# Sheet1.net
KiCad netlist of a schematic drawn in Altium Designer
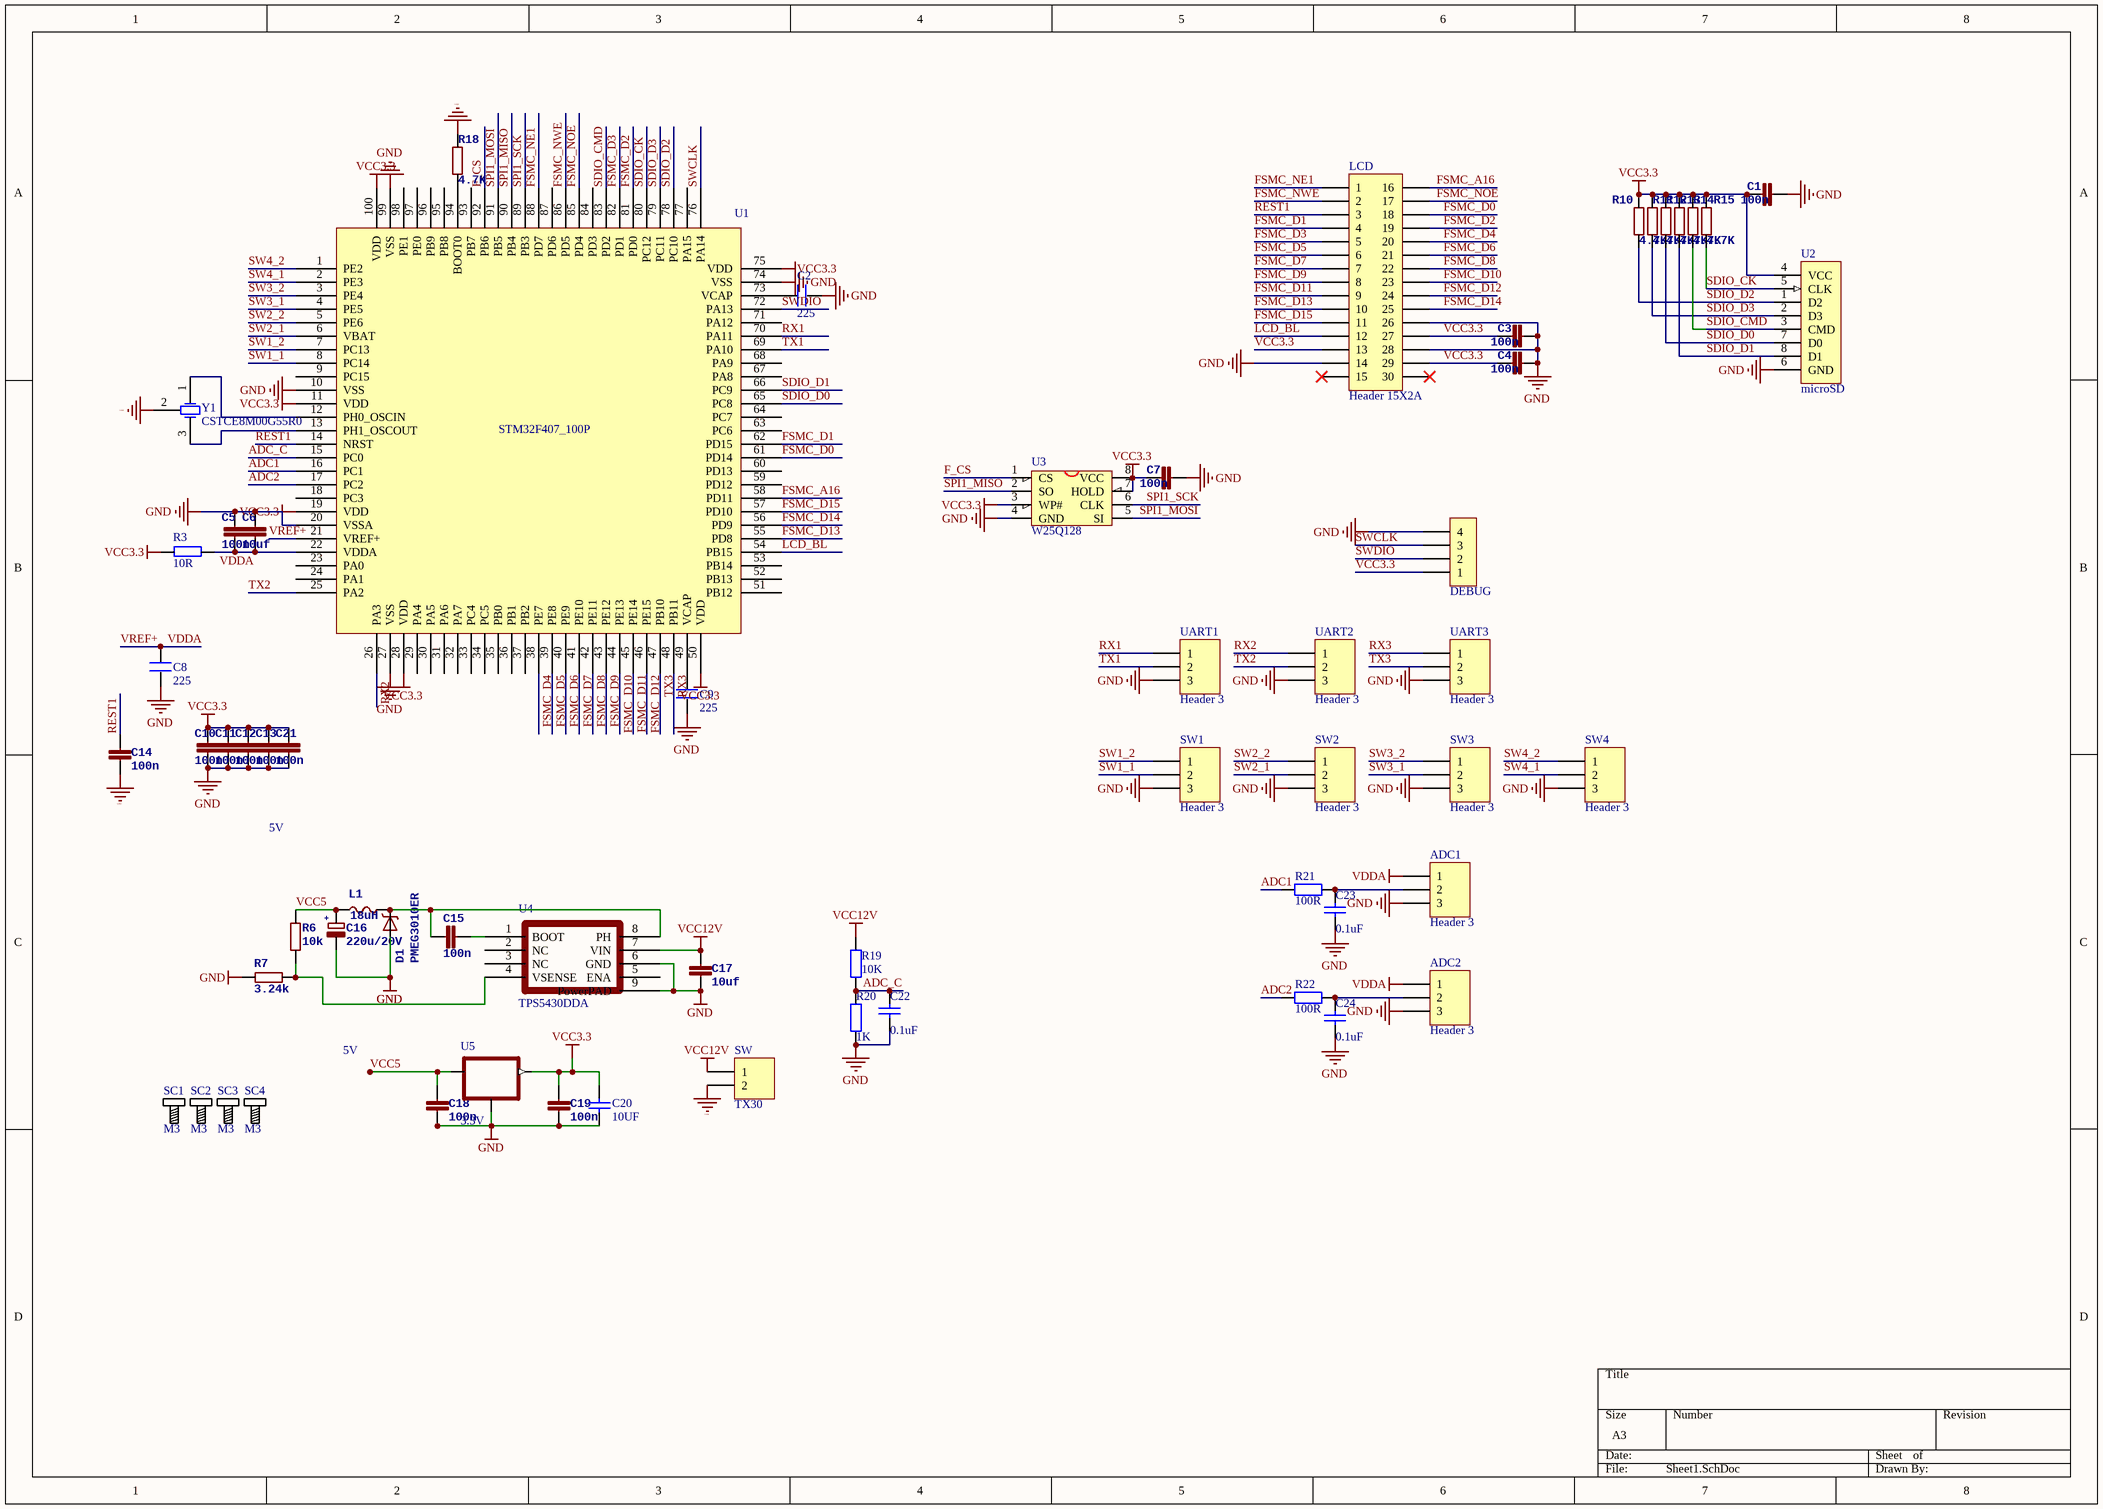
[diagram p0: Sheet1.SchDoc]

(export (version "E")
  (design (tool "Eeschema 10.0.6"))
  (components
    (comp (ref "ADC1")
      (value "Header 3")
      (footprint "3PJST1.25")
      (description "Header, 3-Pin")
      (fields (field (name "PUBLISHER") "Altium Limited"))
      (libsource (lib "Miscellaneous Connectors") (part "Header 3"))
    )
    (comp (ref "ADC2")
      (value "Header 3")
      (footprint "3PJST1.25")
      (description "Header, 3-Pin")
      (fields (field (name "PUBLISHER") "Altium Limited"))
      (libsource (lib "Miscellaneous Connectors") (part "Header 3"))
    )
    (comp (ref "C1")
      (value "100n")
      (footprint "C0603")
      (description "CAPACITOR, European symbol")
      (libsource (lib "") (part "C-EUC0603_1"))
    )
    (comp (ref "C2") (value "225") (footprint "C0603") (libsource (lib "Explorer STM32F407封装库") (part "C")))
    (comp (ref "C3")
      (value "100n")
      (footprint "C0603")
      (description "CAPACITOR, European symbol")
      (libsource (lib "") (part "C-EUC0603_1"))
    )
    (comp (ref "C4")
      (value "100n")
      (footprint "C0603")
      (description "CAPACITOR, European symbol")
      (libsource (lib "") (part "C-EUC0603_1"))
    )
    (comp (ref "C5")
      (value "100n")
      (footprint "C0603")
      (description "CAPACITOR, European symbol")
      (libsource (lib "TZJLIB") (part "C-EUC0603"))
    )
    (comp (ref "C6")
      (value "10uf")
      (footprint "C0603")
      (description "CAPACITOR, European symbol")
      (libsource (lib "TZJLIB") (part "C-EUC0603"))
    )
    (comp (ref "C7")
      (value "100n")
      (footprint "C0603")
      (description "CAPACITOR, European symbol")
      (libsource (lib "") (part "C-EUC0603_1"))
    )
    (comp (ref "C8") (value "225") (footprint "C0603") (libsource (lib "Explorer STM32F407封装库") (part "C")))
    (comp (ref "C9") (value "225") (footprint "C0603") (libsource (lib "Explorer STM32F407封装库") (part "C")))
    (comp (ref "C10")
      (value "100n")
      (footprint "C0603")
      (description "CAPACITOR, European symbol")
      (libsource (lib "TZJLIB") (part "C-EUC0603"))
    )
    (comp (ref "C11")
      (value "100n")
      (footprint "C0603")
      (description "CAPACITOR, European symbol")
      (libsource (lib "TZJLIB") (part "C-EUC0603"))
    )
    (comp (ref "C12")
      (value "100n")
      (footprint "C0603")
      (description "CAPACITOR, European symbol")
      (libsource (lib "TZJLIB") (part "C-EUC0603"))
    )
    (comp (ref "C13")
      (value "100n")
      (footprint "C0603")
      (description "CAPACITOR, European symbol")
      (libsource (lib "TZJLIB") (part "C-EUC0603"))
    )
    (comp (ref "C14")
      (value "100n")
      (footprint "C0603")
      (description "CAPACITOR, European symbol")
      (libsource (lib "TZJLIB") (part "C-EUC0603"))
    )
    (comp (ref "C15")
      (value "100n")
      (footprint "C0603")
      (description "CAPACITOR, European symbol")
      (libsource (lib "") (part "C-EUC0603_1"))
    )
    (comp (ref "C16")
      (value "220u/20V")
      (footprint "SMC_B")
      (description "POLARIZED CAPACITOR, European symbol")
      (fields (field (name "+") "+"))
      (libsource (lib "rcl") (part "CPOL-EUSMCB"))
    )
    (comp (ref "C17")
      (value "10uf")
      (footprint "C0603")
      (description "CAPACITOR, European symbol")
      (libsource (lib "rcl") (part "C-EUC0603"))
    )
    (comp (ref "C18")
      (value "100n")
      (footprint "C0603")
      (description "CAPACITOR, European symbol")
      (libsource (lib "rcl") (part "C-EUC0603"))
    )
    (comp (ref "C19")
      (value "100n")
      (footprint "C0603")
      (description "CAPACITOR, European symbol")
      (libsource (lib "rcl") (part "C-EUC0603"))
    )
    (comp (ref "C20")
      (value "10UF")
      (footprint "C0603")
      (description "Capacitor")
      (fields (field (name "PUBLISHER") "Altium Limited"))
      (libsource (lib "Miscellaneous Devices") (part "Cap"))
    )
    (comp (ref "C21")
      (value "100n")
      (footprint "C0603")
      (description "CAPACITOR, European symbol")
      (libsource (lib "TZJLIB") (part "C-EUC0603"))
    )
    (comp (ref "C22")
      (value "0.1uF")
      (footprint "C0603")
      (description "Capacitor")
      (fields (field (name "PUBLISHER") "Altium Limited"))
      (libsource (lib "Miscellaneous Devices") (part "Cap"))
    )
    (comp (ref "C23")
      (value "0.1uF")
      (footprint "C0603")
      (description "Capacitor")
      (fields (field (name "PUBLISHER") "Altium Limited"))
      (libsource (lib "Miscellaneous Devices") (part "Cap"))
    )
    (comp (ref "C24")
      (value "0.1uF")
      (footprint "C0603")
      (description "Capacitor")
      (fields (field (name "PUBLISHER") "Altium Limited"))
      (libsource (lib "Miscellaneous Devices") (part "Cap"))
    )
    (comp (ref "D1")
      (value "PMEG3010ER")
      (footprint "SOD123W-DIODE - AK")
      (libsource (lib "TZJLIB") (part "DIODE-SCHOTTKYSOD123-W"))
    )
    (comp (ref "DEBUG") (value "CON4") (footprint "DF13-1.25-4A") (libsource (lib "原理图封装库") (part "CON4")))
    (comp (ref "L1") (value "18uH") (footprint "L7_7_4") (libsource (lib "BGC1.0") (part "L-EU_L0603")))
    (comp (ref "LCD")
      (value "Header 15X2A")
      (footprint "DIP1.0X30")
      (description "Header, 15-Pin, Dual row")
      (fields (field (name "PUBLISHER") "Altium Limited"))
      (libsource (lib "Miscellaneous Connectors") (part "Header 15X2A"))
    )
    (comp (ref "R3") (value "10R") (footprint "R0603") (libsource (lib "Explorer STM32F407封装库") (part "R")))
    (comp (ref "R6")
      (value "10k")
      (footprint "R0603")
      (description "RESISTOR, European symbol")
      (libsource (lib "rcl") (part "R-EU_R0603"))
    )
    (comp (ref "R7")
      (value "3.24k")
      (footprint "R0603")
      (description "RESISTOR, European symbol")
      (libsource (lib "rcl") (part "R-EU_R0603"))
    )
    (comp (ref "R10")
      (value "4.7K")
      (footprint "R0603")
      (description "RESISTOR, European symbol")
      (libsource (lib "rcl") (part "R-EU_R0603"))
    )
    (comp (ref "R11")
      (value "4.7K")
      (footprint "R0603")
      (description "RESISTOR, European symbol")
      (libsource (lib "rcl") (part "R-EU_R0603"))
    )
    (comp (ref "R12")
      (value "4.7K")
      (footprint "R0603")
      (description "RESISTOR, European symbol")
      (libsource (lib "rcl") (part "R-EU_R0603"))
    )
    (comp (ref "R13")
      (value "4.7K")
      (footprint "R0603")
      (description "RESISTOR, European symbol")
      (libsource (lib "rcl") (part "R-EU_R0603"))
    )
    (comp (ref "R14")
      (value "4.7K")
      (footprint "R0603")
      (description "RESISTOR, European symbol")
      (libsource (lib "rcl") (part "R-EU_R0603"))
    )
    (comp (ref "R15")
      (value "4.7K")
      (footprint "R0603")
      (description "RESISTOR, European symbol")
      (libsource (lib "rcl") (part "R-EU_R0603"))
    )
    (comp (ref "R18")
      (value "4.7K")
      (footprint "R0603")
      (description "RESISTOR, European symbol")
      (libsource (lib "rcl") (part "R-EU_R0603"))
    )
    (comp (ref "R19")
      (value "10K")
      (footprint "R0603")
      (description "Resistor")
      (fields (field (name "PUBLISHER") "Altium Limited"))
      (libsource (lib "") (part "Res2_1"))
    )
    (comp (ref "R20")
      (value "1K")
      (footprint "R0603")
      (description "Resistor")
      (fields (field (name "Comment") "10K") (field (name "PUBLISHER") "Altium Limited"))
      (libsource (lib "") (part "Res2_1"))
    )
    (comp (ref "R21")
      (value "100R")
      (footprint "R0603")
      (description "Resistor")
      (fields (field (name "Comment") "10K") (field (name "PUBLISHER") "Altium Limited"))
      (libsource (lib "Miscellaneous Devices") (part "Res2"))
    )
    (comp (ref "R22")
      (value "100R")
      (footprint "R0603")
      (description "Resistor")
      (fields (field (name "Comment") "10K") (field (name "PUBLISHER") "Altium Limited"))
      (libsource (lib "Miscellaneous Devices") (part "Res2"))
    )
    (comp (ref "SC1")
      (value "M3")
      (footprint "TZJLIB:SCRREW_M3")
      (description "Screw")
      (libsource (lib "MY") (part "Screw_M3"))
    )
    (comp (ref "SC2")
      (value "M3")
      (footprint "SCRREW_M3")
      (description "Screw")
      (libsource (lib "MY") (part "Screw_M3"))
    )
    (comp (ref "SC3")
      (value "M3")
      (footprint "SCRREW_M3")
      (description "Screw")
      (libsource (lib "MY") (part "Screw_M3"))
    )
    (comp (ref "SC4")
      (value "M3")
      (footprint "SCRREW_M3")
      (description "Screw")
      (libsource (lib "MY") (part "Screw_M3"))
    )
    (comp (ref "SW")
      (value "TX30")
      (footprint "TX30-m")
      (description "Header, 2-Pin")
      (fields (field (name "PUBLISHER") "Altium Limited"))
      (libsource (lib "Miscellaneous Connectors") (part "Header 2"))
    )
    (comp (ref "SW1")
      (value "Header 3")
      (footprint "3PJST1.25")
      (description "Header, 3-Pin")
      (fields (field (name "PUBLISHER") "Altium Limited"))
      (libsource (lib "Miscellaneous Connectors") (part "Header 3"))
    )
    (comp (ref "SW2")
      (value "Header 3")
      (footprint "3PJST1.25")
      (description "Header, 3-Pin")
      (fields (field (name "PUBLISHER") "Altium Limited"))
      (libsource (lib "Miscellaneous Connectors") (part "Header 3"))
    )
    (comp (ref "SW3")
      (value "Header 3")
      (footprint "3PJST1.25")
      (description "Header, 3-Pin")
      (fields (field (name "PUBLISHER") "Altium Limited"))
      (libsource (lib "Miscellaneous Connectors") (part "Header 3"))
    )
    (comp (ref "SW4")
      (value "Header 3")
      (footprint "3PJST1.25")
      (description "Header, 3-Pin")
      (fields (field (name "PUBLISHER") "Altium Limited"))
      (libsource (lib "Miscellaneous Connectors") (part "Header 3"))
    )
    (comp (ref "U1")
      (value "STM32F407_100P")
      (footprint "ST_LQFP100")
      (libsource (lib "TZJLIB") (part "STM32F407_100P"))
    )
    (comp (ref "U2")
      (value "microSD")
      (footprint "MICROSD1")
      (libsource (lib "004-Controller") (part "microSD"))
    )
    (comp (ref "U3")
      (value "W25Q128")
      (footprint "SOIC-8")
      (description "W25X16;SST25VF016;MX25L1605")
      (libsource (lib "TZJLIB") (part "W25X16"))
    )
    (comp (ref "U4") (value "TPS5430DDA") (footprint "SOIC") (libsource (lib "BGC1.0") (part "TPS5430DDA")))
    (comp (ref "U5") (value "3.3V") (footprint "SOT23") (libsource (lib "BGC1.0") (part "XC6206")))
    (comp (ref "UART1")
      (value "Header 3")
      (footprint "3PJST1.25")
      (description "Header, 3-Pin")
      (fields (field (name "PUBLISHER") "Altium Limited"))
      (libsource (lib "Miscellaneous Connectors") (part "Header 3"))
    )
    (comp (ref "UART2")
      (value "Header 3")
      (footprint "3PJST1.25")
      (description "Header, 3-Pin")
      (fields (field (name "PUBLISHER") "Altium Limited"))
      (libsource (lib "Miscellaneous Connectors") (part "Header 3"))
    )
    (comp (ref "UART3")
      (value "Header 3")
      (footprint "3PJST1.25")
      (description "Header, 3-Pin")
      (fields (field (name "PUBLISHER") "Altium Limited"))
      (libsource (lib "Miscellaneous Connectors") (part "Header 3"))
    )
    (comp (ref "Y1")
      (value "CSTCE8M00G55R0")
      (footprint "CRYSMD3.2X1.3")
      (libsource (lib "airtops-L") (part "XTAL-3"))
    )
  )
  (nets
    (net (code "1") (name "/ADC1") (class "Default")
      (node (ref "R21") (pin "1") (pinfunction "1_1") (pintype "passive"))
      (node (ref "U1") (pin "16") (pinfunction "PC1_16") (pintype "passive"))
    )
    (net (code "2") (name "/ADC2") (class "Default")
      (node (ref "R22") (pin "1") (pinfunction "1_1") (pintype "passive"))
      (node (ref "U1") (pin "17") (pinfunction "PC2_17") (pintype "passive"))
    )
    (net (code "3") (name "/ADC_C") (class "Default")
      (node (ref "C22") (pin "2") (pinfunction "2_2") (pintype "passive"))
      (node (ref "R19") (pin "2") (pinfunction "2_2") (pintype "passive"))
      (node (ref "R20") (pin "1") (pinfunction "1_1") (pintype "passive"))
      (node (ref "U1") (pin "15") (pinfunction "PC0_15") (pintype "passive"))
    )
    (net (code "4") (name "/FSMC_A16") (class "Default")
      (node (ref "LCD") (pin "16") (pinfunction "16_16") (pintype "passive"))
      (node (ref "U1") (pin "58") (pinfunction "PD11_58") (pintype "passive"))
    )
    (net (code "5") (name "/FSMC_D0") (class "Default")
      (node (ref "LCD") (pin "18") (pinfunction "18_18") (pintype "passive"))
      (node (ref "U1") (pin "61") (pinfunction "PD14_61") (pintype "passive"))
    )
    (net (code "6") (name "/FSMC_D1") (class "Default")
      (node (ref "LCD") (pin "4") (pinfunction "4_4") (pintype "passive"))
      (node (ref "U1") (pin "62") (pinfunction "PD15_62") (pintype "passive"))
    )
    (net (code "7") (name "/FSMC_D2") (class "Default")
      (node (ref "LCD") (pin "19") (pinfunction "19_19") (pintype "passive"))
      (node (ref "U1") (pin "81") (pinfunction "PD0_81") (pintype "passive"))
    )
    (net (code "8") (name "/FSMC_D3") (class "Default")
      (node (ref "LCD") (pin "5") (pinfunction "5_5") (pintype "passive"))
      (node (ref "U1") (pin "82") (pinfunction "PD1_82") (pintype "passive"))
    )
    (net (code "9") (name "/FSMC_D4") (class "Default")
      (node (ref "LCD") (pin "20") (pinfunction "20_20") (pintype "passive"))
      (node (ref "U1") (pin "38") (pinfunction "PE7_38") (pintype "passive"))
    )
    (net (code "10") (name "/FSMC_D5") (class "Default")
      (node (ref "LCD") (pin "6") (pinfunction "6_6") (pintype "passive"))
      (node (ref "U1") (pin "39") (pinfunction "PE8_39") (pintype "passive"))
    )
    (net (code "11") (name "/FSMC_D6") (class "Default")
      (node (ref "LCD") (pin "21") (pinfunction "21_21") (pintype "passive"))
      (node (ref "U1") (pin "40") (pinfunction "PE9_40") (pintype "passive"))
    )
    (net (code "12") (name "/FSMC_D7") (class "Default")
      (node (ref "LCD") (pin "7") (pinfunction "7_7") (pintype "passive"))
      (node (ref "U1") (pin "41") (pinfunction "PE10_41") (pintype "passive"))
    )
    (net (code "13") (name "/FSMC_D8") (class "Default")
      (node (ref "LCD") (pin "22") (pinfunction "22_22") (pintype "passive"))
      (node (ref "U1") (pin "42") (pinfunction "PE11_42") (pintype "passive"))
    )
    (net (code "14") (name "/FSMC_D9") (class "Default")
      (node (ref "LCD") (pin "8") (pinfunction "8_8") (pintype "passive"))
      (node (ref "U1") (pin "43") (pinfunction "PE12_43") (pintype "passive"))
    )
    (net (code "15") (name "/FSMC_D10") (class "Default")
      (node (ref "LCD") (pin "23") (pinfunction "23_23") (pintype "passive"))
      (node (ref "U1") (pin "44") (pinfunction "PE13_44") (pintype "passive"))
    )
    (net (code "16") (name "/FSMC_D11") (class "Default")
      (node (ref "LCD") (pin "9") (pinfunction "9_9") (pintype "passive"))
      (node (ref "U1") (pin "45") (pinfunction "PE14_45") (pintype "passive"))
    )
    (net (code "17") (name "/FSMC_D12") (class "Default")
      (node (ref "LCD") (pin "24") (pinfunction "24_24") (pintype "passive"))
      (node (ref "U1") (pin "46") (pinfunction "PE15_46") (pintype "passive"))
    )
    (net (code "18") (name "/FSMC_D13") (class "Default")
      (node (ref "LCD") (pin "10") (pinfunction "10_10") (pintype "passive"))
      (node (ref "U1") (pin "55") (pinfunction "PD8_55") (pintype "passive"))
    )
    (net (code "19") (name "/FSMC_D14") (class "Default")
      (node (ref "LCD") (pin "25") (pinfunction "25_25") (pintype "passive"))
      (node (ref "U1") (pin "56") (pinfunction "PD9_56") (pintype "passive"))
    )
    (net (code "20") (name "/FSMC_D15") (class "Default")
      (node (ref "LCD") (pin "11") (pinfunction "11_11") (pintype "passive"))
      (node (ref "U1") (pin "57") (pinfunction "PD10_57") (pintype "passive"))
    )
    (net (code "21") (name "/FSMC_NE1") (class "Default")
      (node (ref "LCD") (pin "1") (pinfunction "1_1") (pintype "passive"))
      (node (ref "U1") (pin "88") (pinfunction "PD7_88") (pintype "passive"))
    )
    (net (code "22") (name "/FSMC_NOE") (class "Default")
      (node (ref "LCD") (pin "17") (pinfunction "17_17") (pintype "passive"))
      (node (ref "U1") (pin "85") (pinfunction "PD4_85") (pintype "passive"))
    )
    (net (code "23") (name "/FSMC_NWE") (class "Default")
      (node (ref "LCD") (pin "2") (pinfunction "2_2") (pintype "passive"))
      (node (ref "U1") (pin "86") (pinfunction "PD5_86") (pintype "passive"))
    )
    (net (code "24") (name "/F_CS") (class "Default")
      (node (ref "U1") (pin "92") (pinfunction "PB6_92") (pintype "passive"))
      (node (ref "U3") (pin "1") (pinfunction "CS_1") (pintype "passive"))
    )
    (net (code "25") (name "/LCD_BL") (class "Default")
      (node (ref "LCD") (pin "12") (pinfunction "12_12") (pintype "passive"))
      (node (ref "U1") (pin "54") (pinfunction "PB15_54") (pintype "passive"))
    )
    (net (code "26") (name "/REST1") (class "Default")
      (node (ref "C14") (pin "2") (pinfunction "2_2") (pintype "passive"))
      (node (ref "LCD") (pin "3") (pinfunction "3_3") (pintype "passive"))
      (node (ref "U1") (pin "14") (pinfunction "NRST_14") (pintype "passive"))
    )
    (net (code "27") (name "/RX1") (class "Default")
      (node (ref "U1") (pin "70") (pinfunction "PA11_70") (pintype "passive"))
      (node (ref "UART1") (pin "1") (pinfunction "1_1") (pintype "passive"))
    )
    (net (code "28") (name "/RX2") (class "Default")
      (node (ref "U1") (pin "26") (pinfunction "PA3_26") (pintype "passive"))
      (node (ref "UART2") (pin "1") (pinfunction "1_1") (pintype "passive"))
    )
    (net (code "29") (name "/RX3") (class "Default")
      (node (ref "U1") (pin "48") (pinfunction "PB11_48") (pintype "passive"))
      (node (ref "UART3") (pin "1") (pinfunction "1_1") (pintype "passive"))
    )
    (net (code "30") (name "/SDIO_CK") (class "Default")
      (node (ref "R15") (pin "1") (pinfunction "1_1") (pintype "passive"))
      (node (ref "U1") (pin "80") (pinfunction "PC12_80") (pintype "passive"))
      (node (ref "U2") (pin "5") (pinfunction "CLK_5") (pintype "input"))
    )
    (net (code "31") (name "/SDIO_CMD") (class "Default")
      (node (ref "R14") (pin "1") (pinfunction "1_1") (pintype "passive"))
      (node (ref "U1") (pin "83") (pinfunction "PD2_83") (pintype "passive"))
      (node (ref "U2") (pin "3") (pinfunction "CMD_3") (pintype "passive"))
    )
    (net (code "32") (name "/SDIO_D0") (class "Default")
      (node (ref "R12") (pin "1") (pinfunction "1_1") (pintype "passive"))
      (node (ref "U1") (pin "65") (pinfunction "PC8_65") (pintype "passive"))
      (node (ref "U2") (pin "7") (pinfunction "D0_7") (pintype "passive"))
    )
    (net (code "33") (name "/SDIO_D1") (class "Default")
      (node (ref "R13") (pin "1") (pinfunction "1_1") (pintype "passive"))
      (node (ref "U1") (pin "66") (pinfunction "PC9_66") (pintype "passive"))
      (node (ref "U2") (pin "8") (pinfunction "D1_8") (pintype "passive"))
    )
    (net (code "34") (name "/SDIO_D2") (class "Default")
      (node (ref "R10") (pin "1") (pinfunction "1_1") (pintype "passive"))
      (node (ref "U1") (pin "78") (pinfunction "PC10_78") (pintype "passive"))
      (node (ref "U2") (pin "1") (pinfunction "D2_1") (pintype "passive"))
    )
    (net (code "35") (name "/SDIO_D3") (class "Default")
      (node (ref "R11") (pin "1") (pinfunction "1_1") (pintype "passive"))
      (node (ref "U1") (pin "79") (pinfunction "PC11_79") (pintype "passive"))
      (node (ref "U2") (pin "2") (pinfunction "D3_2") (pintype "passive"))
    )
    (net (code "36") (name "/SPI1_MISO") (class "Default")
      (node (ref "U1") (pin "90") (pinfunction "PB4_90") (pintype "passive"))
      (node (ref "U3") (pin "2") (pinfunction "SO_2") (pintype "passive"))
    )
    (net (code "37") (name "/SPI1_MOSI") (class "Default")
      (node (ref "U1") (pin "91") (pinfunction "PB5_91") (pintype "passive"))
      (node (ref "U3") (pin "5") (pinfunction "SI_5") (pintype "passive"))
    )
    (net (code "38") (name "/SPI1_SCK") (class "Default")
      (node (ref "U1") (pin "89") (pinfunction "PB3_89") (pintype "passive"))
      (node (ref "U3") (pin "6") (pinfunction "CLK_6") (pintype "passive"))
    )
    (net (code "39") (name "/SW1_1") (class "Default")
      (node (ref "SW1") (pin "2") (pinfunction "2_2") (pintype "passive"))
      (node (ref "U1") (pin "8") (pinfunction "PC14_8") (pintype "passive"))
    )
    (net (code "40") (name "/SW1_2") (class "Default")
      (node (ref "SW1") (pin "1") (pinfunction "1_1") (pintype "passive"))
      (node (ref "U1") (pin "7") (pinfunction "PC13_7") (pintype "passive"))
    )
    (net (code "41") (name "/SW2_1") (class "Default")
      (node (ref "SW2") (pin "2") (pinfunction "2_2") (pintype "passive"))
      (node (ref "U1") (pin "6") (pinfunction "VBAT_6") (pintype "passive"))
    )
    (net (code "42") (name "/SW2_2") (class "Default")
      (node (ref "SW2") (pin "1") (pinfunction "1_1") (pintype "passive"))
      (node (ref "U1") (pin "5") (pinfunction "PE6_5") (pintype "passive"))
    )
    (net (code "43") (name "/SW3_1") (class "Default")
      (node (ref "SW3") (pin "2") (pinfunction "2_2") (pintype "passive"))
      (node (ref "U1") (pin "4") (pinfunction "PE5_4") (pintype "passive"))
    )
    (net (code "44") (name "/SW3_2") (class "Default")
      (node (ref "SW3") (pin "1") (pinfunction "1_1") (pintype "passive"))
      (node (ref "U1") (pin "3") (pinfunction "PE4_3") (pintype "passive"))
    )
    (net (code "45") (name "/SW4_1") (class "Default")
      (node (ref "SW4") (pin "2") (pinfunction "2_2") (pintype "passive"))
      (node (ref "U1") (pin "2") (pinfunction "PE3_2") (pintype "passive"))
    )
    (net (code "46") (name "/SW4_2") (class "Default")
      (node (ref "SW4") (pin "1") (pinfunction "1_1") (pintype "passive"))
      (node (ref "U1") (pin "1") (pinfunction "PE2_1") (pintype "passive"))
    )
    (net (code "47") (name "/SWCLK") (class "Default")
      (node (ref "DEBUG") (pin "3") (pinfunction "3_3") (pintype "passive"))
      (node (ref "U1") (pin "76") (pinfunction "PA14_76") (pintype "passive"))
    )
    (net (code "48") (name "/SWDIO") (class "Default")
      (node (ref "DEBUG") (pin "2") (pinfunction "2_2") (pintype "passive"))
      (node (ref "U1") (pin "72") (pinfunction "PA13_72") (pintype "passive"))
    )
    (net (code "49") (name "/TX1") (class "Default")
      (node (ref "U1") (pin "69") (pinfunction "PA10_69") (pintype "passive"))
      (node (ref "UART1") (pin "2") (pinfunction "2_2") (pintype "passive"))
    )
    (net (code "50") (name "/TX2") (class "Default")
      (node (ref "U1") (pin "25") (pinfunction "PA2_25") (pintype "passive"))
      (node (ref "UART2") (pin "2") (pinfunction "2_2") (pintype "passive"))
    )
    (net (code "51") (name "/TX3") (class "Default")
      (node (ref "U1") (pin "47") (pinfunction "PB10_47") (pintype "passive"))
      (node (ref "UART3") (pin "2") (pinfunction "2_2") (pintype "passive"))
    )
    (net (code "52") (name "/VCC5") (class "Default")
      (node (ref "C16") (pin "+") (pinfunction "+_+") (pintype "passive"))
      (node (ref "C18") (pin "1") (pinfunction "1_1") (pintype "passive"))
      (node (ref "L1") (pin "1") (pinfunction "1_1") (pintype "passive"))
      (node (ref "R6") (pin "2") (pinfunction "2_2") (pintype "passive"))
      (node (ref "U5") (pin "3") (pinfunction "IN_3") (pintype "passive"))
    )
    (net (code "53") (name "GND") (class "Default")
      (node (ref "ADC1") (pin "3") (pinfunction "3_3") (pintype "passive"))
      (node (ref "ADC2") (pin "3") (pinfunction "3_3") (pintype "passive"))
      (node (ref "C1") (pin "2") (pinfunction "2_2") (pintype "passive"))
      (node (ref "C10") (pin "1") (pinfunction "1_1") (pintype "passive"))
      (node (ref "C11") (pin "1") (pinfunction "1_1") (pintype "passive"))
      (node (ref "C12") (pin "1") (pinfunction "1_1") (pintype "passive"))
      (node (ref "C13") (pin "1") (pinfunction "1_1") (pintype "passive"))
      (node (ref "C14") (pin "1") (pinfunction "1_1") (pintype "passive"))
      (node (ref "C16") (pin "-") (pinfunction "-_-") (pintype "passive"))
      (node (ref "C17") (pin "2") (pinfunction "2_2") (pintype "passive"))
      (node (ref "C18") (pin "2") (pinfunction "2_2") (pintype "passive"))
      (node (ref "C19") (pin "2") (pinfunction "2_2") (pintype "passive"))
      (node (ref "C2") (pin "1") (pintype "passive"))
      (node (ref "C20") (pin "1") (pinfunction "1_1") (pintype "passive"))
      (node (ref "C21") (pin "1") (pinfunction "1_1") (pintype "passive"))
      (node (ref "C22") (pin "1") (pinfunction "1_1") (pintype "passive"))
      (node (ref "C23") (pin "1") (pinfunction "1_1") (pintype "passive"))
      (node (ref "C24") (pin "1") (pinfunction "1_1") (pintype "passive"))
      (node (ref "C3") (pin "2") (pinfunction "2_2") (pintype "passive"))
      (node (ref "C4") (pin "2") (pinfunction "2_2") (pintype "passive"))
      (node (ref "C5") (pin "2") (pinfunction "2_2") (pintype "passive"))
      (node (ref "C6") (pin "2") (pinfunction "2_2") (pintype "passive"))
      (node (ref "C7") (pin "2") (pinfunction "2_2") (pintype "passive"))
      (node (ref "C8") (pin "2") (pintype "passive"))
      (node (ref "C9") (pin "1") (pintype "passive"))
      (node (ref "D1") (pin "A") (pinfunction "A_A") (pintype "passive"))
      (node (ref "DEBUG") (pin "4") (pinfunction "4_4") (pintype "passive"))
      (node (ref "LCD") (pin "14") (pinfunction "14_14") (pintype "passive"))
      (node (ref "LCD") (pin "26") (pinfunction "26_26") (pintype "passive"))
      (node (ref "LCD") (pin "28") (pinfunction "28_28") (pintype "passive"))
      (node (ref "R18") (pin "2") (pinfunction "2_2") (pintype "passive"))
      (node (ref "R20") (pin "2") (pinfunction "2_2") (pintype "passive"))
      (node (ref "R7") (pin "2") (pinfunction "2_2") (pintype "passive"))
      (node (ref "SW") (pin "2") (pinfunction "2_2") (pintype "passive"))
      (node (ref "SW1") (pin "3") (pinfunction "3_3") (pintype "passive"))
      (node (ref "SW2") (pin "3") (pinfunction "3_3") (pintype "passive"))
      (node (ref "SW3") (pin "3") (pinfunction "3_3") (pintype "passive"))
      (node (ref "SW4") (pin "3") (pinfunction "3_3") (pintype "passive"))
      (node (ref "U1") (pin "10") (pinfunction "VSS_10") (pintype "passive"))
      (node (ref "U1") (pin "20") (pinfunction "VSSA_20") (pintype "passive"))
      (node (ref "U1") (pin "27") (pinfunction "VSS_27") (pintype "passive"))
      (node (ref "U1") (pin "74") (pinfunction "VSS_74") (pintype "passive"))
      (node (ref "U1") (pin "99") (pinfunction "VSS_99") (pintype "passive"))
      (node (ref "U2") (pin "6") (pinfunction "GND_6") (pintype "passive"))
      (node (ref "U3") (pin "4") (pinfunction "GND_4") (pintype "passive"))
      (node (ref "U4") (pin "6") (pinfunction "GND_6") (pintype "passive"))
      (node (ref "U4") (pin "9") (pinfunction "PowerPAD_9") (pintype "passive"))
      (node (ref "U5") (pin "1") (pinfunction "GND_1") (pintype "passive"))
      (node (ref "UART1") (pin "3") (pinfunction "3_3") (pintype "passive"))
      (node (ref "UART2") (pin "3") (pinfunction "3_3") (pintype "passive"))
      (node (ref "UART3") (pin "3") (pinfunction "3_3") (pintype "passive"))
      (node (ref "Y1") (pin "2") (pinfunction "GND_2") (pintype "passive"))
    )
    (net (code "54") (name "Net-(ADC1-Pad2)") (class "Default")
      (node (ref "ADC1") (pin "2") (pinfunction "2_2") (pintype "passive"))
      (node (ref "C23") (pin "2") (pinfunction "2_2") (pintype "passive"))
      (node (ref "R21") (pin "2") (pinfunction "2_2") (pintype "passive"))
    )
    (net (code "55") (name "Net-(ADC2-Pad2)") (class "Default")
      (node (ref "ADC2") (pin "2") (pinfunction "2_2") (pintype "passive"))
      (node (ref "C24") (pin "2") (pinfunction "2_2") (pintype "passive"))
      (node (ref "R22") (pin "2") (pinfunction "2_2") (pintype "passive"))
    )
    (net (code "56") (name "Net-(C2-Pad2)") (class "Default")
      (node (ref "C2") (pin "2") (pintype "passive"))
      (node (ref "U1") (pin "73") (pinfunction "VCAP_73") (pintype "passive"))
    )
    (net (code "57") (name "Net-(C9-Pad2)") (class "Default")
      (node (ref "C9") (pin "2") (pintype "passive"))
      (node (ref "U1") (pin "49") (pinfunction "VCAP_49") (pintype "passive"))
    )
    (net (code "58") (name "Net-(U1-BOOT0)") (class "Default")
      (node (ref "R18") (pin "1") (pinfunction "1_1") (pintype "passive"))
      (node (ref "U1") (pin "94") (pinfunction "BOOT0_94") (pintype "passive"))
    )
    (net (code "59") (name "Net-(U1-PH0_OSCIN)") (class "Default")
      (node (ref "U1") (pin "12") (pinfunction "PH0_OSCIN_12") (pintype "passive"))
      (node (ref "Y1") (pin "1") (pinfunction "OSC1_1") (pintype "passive"))
    )
    (net (code "60") (name "Net-(U1-PH1_OSCOUT)") (class "Default")
      (node (ref "U1") (pin "13") (pinfunction "PH1_OSCOUT_13") (pintype "passive"))
      (node (ref "Y1") (pin "3") (pinfunction "OSC2_3") (pintype "passive"))
    )
    (net (code "61") (name "Net-(U4-BOOT)") (class "Default")
      (node (ref "C15") (pin "2") (pinfunction "2_2") (pintype "passive"))
      (node (ref "U4") (pin "1") (pinfunction "BOOT_1") (pintype "passive"))
    )
    (net (code "62") (name "Net-(U4-PH)") (class "Default")
      (node (ref "C15") (pin "1") (pinfunction "1_1") (pintype "passive"))
      (node (ref "D1") (pin "K") (pinfunction "K_K") (pintype "passive"))
      (node (ref "L1") (pin "2") (pinfunction "2_2") (pintype "passive"))
      (node (ref "U4") (pin "8") (pinfunction "PH_8") (pintype "passive"))
    )
    (net (code "63") (name "Net-(U4-VSENSE)") (class "Default")
      (node (ref "R6") (pin "1") (pinfunction "1_1") (pintype "passive"))
      (node (ref "R7") (pin "1") (pinfunction "1_1") (pintype "passive"))
      (node (ref "U4") (pin "4") (pinfunction "VSENSE_4") (pintype "passive"))
    )
    (net (code "64") (name "VCC3.3") (class "Default")
      (node (ref "C1") (pin "1") (pinfunction "1_1") (pintype "passive"))
      (node (ref "C10") (pin "2") (pinfunction "2_2") (pintype "passive"))
      (node (ref "C11") (pin "2") (pinfunction "2_2") (pintype "passive"))
      (node (ref "C12") (pin "2") (pinfunction "2_2") (pintype "passive"))
      (node (ref "C13") (pin "2") (pinfunction "2_2") (pintype "passive"))
      (node (ref "C19") (pin "1") (pinfunction "1_1") (pintype "passive"))
      (node (ref "C20") (pin "2") (pinfunction "2_2") (pintype "passive"))
      (node (ref "C21") (pin "2") (pinfunction "2_2") (pintype "passive"))
      (node (ref "C3") (pin "1") (pinfunction "1_1") (pintype "passive"))
      (node (ref "C4") (pin "1") (pinfunction "1_1") (pintype "passive"))
      (node (ref "C7") (pin "1") (pinfunction "1_1") (pintype "passive"))
      (node (ref "DEBUG") (pin "1") (pinfunction "1_1") (pintype "passive"))
      (node (ref "LCD") (pin "13") (pinfunction "13_13") (pintype "passive"))
      (node (ref "LCD") (pin "27") (pinfunction "27_27") (pintype "passive"))
      (node (ref "LCD") (pin "29") (pinfunction "29_29") (pintype "passive"))
      (node (ref "R10") (pin "2") (pinfunction "2_2") (pintype "passive"))
      (node (ref "R11") (pin "2") (pinfunction "2_2") (pintype "passive"))
      (node (ref "R12") (pin "2") (pinfunction "2_2") (pintype "passive"))
      (node (ref "R13") (pin "2") (pinfunction "2_2") (pintype "passive"))
      (node (ref "R14") (pin "2") (pinfunction "2_2") (pintype "passive"))
      (node (ref "R15") (pin "2") (pinfunction "2_2") (pintype "passive"))
      (node (ref "R3") (pin "2") (pintype "passive"))
      (node (ref "U1") (pin "100") (pinfunction "VDD_100") (pintype "passive"))
      (node (ref "U1") (pin "11") (pinfunction "VDD_11") (pintype "passive"))
      (node (ref "U1") (pin "19") (pinfunction "VDD_19") (pintype "passive"))
      (node (ref "U1") (pin "28") (pinfunction "VDD_28") (pintype "passive"))
      (node (ref "U1") (pin "50") (pinfunction "VDD_50") (pintype "passive"))
      (node (ref "U1") (pin "75") (pinfunction "VDD_75") (pintype "passive"))
      (node (ref "U2") (pin "4") (pinfunction "VCC_4") (pintype "passive"))
      (node (ref "U3") (pin "3") (pinfunction "WP#_3") (pintype "passive"))
      (node (ref "U3") (pin "7") (pinfunction "HOLD_7") (pintype "passive"))
      (node (ref "U3") (pin "8") (pinfunction "VCC_8") (pintype "passive"))
      (node (ref "U5") (pin "2") (pinfunction "OUT_2") (pintype "output"))
    )
    (net (code "65") (name "VCC12V") (class "Default")
      (node (ref "C17") (pin "1") (pinfunction "1_1") (pintype "passive"))
      (node (ref "R19") (pin "1") (pinfunction "1_1") (pintype "passive"))
      (node (ref "SW") (pin "1") (pinfunction "1_1") (pintype "passive"))
      (node (ref "U4") (pin "7") (pinfunction "VIN_7") (pintype "passive"))
    )
    (net (code "66") (name "VDDA") (class "Default")
      (node (ref "ADC1") (pin "1") (pinfunction "1_1") (pintype "passive"))
      (node (ref "ADC2") (pin "1") (pinfunction "1_1") (pintype "passive"))
      (node (ref "C5") (pin "1") (pinfunction "1_1") (pintype "passive"))
      (node (ref "C6") (pin "1") (pinfunction "1_1") (pintype "passive"))
      (node (ref "C8") (pin "1") (pintype "passive"))
      (node (ref "R3") (pin "1") (pintype "passive"))
      (node (ref "U1") (pin "21") (pinfunction "VREF+_21") (pintype "passive"))
      (node (ref "U1") (pin "22") (pinfunction "VDDA_22") (pintype "passive"))
    )
    (net (code "67") (name "unconnected-(LCD-Pad15)") (class "Default")
      (node (ref "LCD") (pin "15") (pinfunction "15_15") (pintype "passive+no_connect"))
    )
    (net (code "68") (name "unconnected-(LCD-Pad30)") (class "Default")
      (node (ref "LCD") (pin "30") (pinfunction "30_30") (pintype "passive+no_connect"))
    )
    (net (code "69") (name "unconnected-(U1-PA0-Pad23)") (class "Default")
      (node (ref "U1") (pin "23") (pinfunction "PA0_23") (pintype "passive"))
    )
    (net (code "70") (name "unconnected-(U1-PA1-Pad24)") (class "Default")
      (node (ref "U1") (pin "24") (pinfunction "PA1_24") (pintype "passive"))
    )
    (net (code "71") (name "unconnected-(U1-PA4-Pad29)") (class "Default")
      (node (ref "U1") (pin "29") (pinfunction "PA4_29") (pintype "passive"))
    )
    (net (code "72") (name "unconnected-(U1-PA5-Pad30)") (class "Default")
      (node (ref "U1") (pin "30") (pinfunction "PA5_30") (pintype "passive"))
    )
    (net (code "73") (name "unconnected-(U1-PA6-Pad31)") (class "Default")
      (node (ref "U1") (pin "31") (pinfunction "PA6_31") (pintype "passive"))
    )
    (net (code "74") (name "unconnected-(U1-PA7-Pad32)") (class "Default")
      (node (ref "U1") (pin "32") (pinfunction "PA7_32") (pintype "passive"))
    )
    (net (code "75") (name "unconnected-(U1-PA8-Pad67)") (class "Default")
      (node (ref "U1") (pin "67") (pinfunction "PA8_67") (pintype "passive"))
    )
    (net (code "76") (name "unconnected-(U1-PA9-Pad68)") (class "Default")
      (node (ref "U1") (pin "68") (pinfunction "PA9_68") (pintype "passive"))
    )
    (net (code "77") (name "unconnected-(U1-PA12-Pad71)") (class "Default")
      (node (ref "U1") (pin "71") (pinfunction "PA12_71") (pintype "passive"))
    )
    (net (code "78") (name "unconnected-(U1-PA15-Pad77)") (class "Default")
      (node (ref "U1") (pin "77") (pinfunction "PA15_77") (pintype "passive"))
    )
    (net (code "79") (name "unconnected-(U1-PB0-Pad35)") (class "Default")
      (node (ref "U1") (pin "35") (pinfunction "PB0_35") (pintype "passive"))
    )
    (net (code "80") (name "unconnected-(U1-PB1-Pad36)") (class "Default")
      (node (ref "U1") (pin "36") (pinfunction "PB1_36") (pintype "passive"))
    )
    (net (code "81") (name "unconnected-(U1-PB2-Pad37)") (class "Default")
      (node (ref "U1") (pin "37") (pinfunction "PB2_37") (pintype "passive"))
    )
    (net (code "82") (name "unconnected-(U1-PB7-Pad93)") (class "Default")
      (node (ref "U1") (pin "93") (pinfunction "PB7_93") (pintype "passive"))
    )
    (net (code "83") (name "unconnected-(U1-PB8-Pad95)") (class "Default")
      (node (ref "U1") (pin "95") (pinfunction "PB8_95") (pintype "passive"))
    )
    (net (code "84") (name "unconnected-(U1-PB9-Pad96)") (class "Default")
      (node (ref "U1") (pin "96") (pinfunction "PB9_96") (pintype "passive"))
    )
    (net (code "85") (name "unconnected-(U1-PB12-Pad51)") (class "Default")
      (node (ref "U1") (pin "51") (pinfunction "PB12_51") (pintype "passive"))
    )
    (net (code "86") (name "unconnected-(U1-PB13-Pad52)") (class "Default")
      (node (ref "U1") (pin "52") (pinfunction "PB13_52") (pintype "passive"))
    )
    (net (code "87") (name "unconnected-(U1-PB14-Pad53)") (class "Default")
      (node (ref "U1") (pin "53") (pinfunction "PB14_53") (pintype "passive"))
    )
    (net (code "88") (name "unconnected-(U1-PC3-Pad18)") (class "Default")
      (node (ref "U1") (pin "18") (pinfunction "PC3_18") (pintype "passive"))
    )
    (net (code "89") (name "unconnected-(U1-PC4-Pad33)") (class "Default")
      (node (ref "U1") (pin "33") (pinfunction "PC4_33") (pintype "passive"))
    )
    (net (code "90") (name "unconnected-(U1-PC5-Pad34)") (class "Default")
      (node (ref "U1") (pin "34") (pinfunction "PC5_34") (pintype "passive"))
    )
    (net (code "91") (name "unconnected-(U1-PC6-Pad63)") (class "Default")
      (node (ref "U1") (pin "63") (pinfunction "PC6_63") (pintype "passive"))
    )
    (net (code "92") (name "unconnected-(U1-PC7-Pad64)") (class "Default")
      (node (ref "U1") (pin "64") (pinfunction "PC7_64") (pintype "passive"))
    )
    (net (code "93") (name "unconnected-(U1-PC15-Pad9)") (class "Default")
      (node (ref "U1") (pin "9") (pinfunction "PC15_9") (pintype "passive"))
    )
    (net (code "94") (name "unconnected-(U1-PD3-Pad84)") (class "Default")
      (node (ref "U1") (pin "84") (pinfunction "PD3_84") (pintype "passive"))
    )
    (net (code "95") (name "unconnected-(U1-PD6-Pad87)") (class "Default")
      (node (ref "U1") (pin "87") (pinfunction "PD6_87") (pintype "passive"))
    )
    (net (code "96") (name "unconnected-(U1-PD12-Pad59)") (class "Default")
      (node (ref "U1") (pin "59") (pinfunction "PD12_59") (pintype "passive"))
    )
    (net (code "97") (name "unconnected-(U1-PD13-Pad60)") (class "Default")
      (node (ref "U1") (pin "60") (pinfunction "PD13_60") (pintype "passive"))
    )
    (net (code "98") (name "unconnected-(U1-PE0-Pad97)") (class "Default")
      (node (ref "U1") (pin "97") (pinfunction "PE0_97") (pintype "passive"))
    )
    (net (code "99") (name "unconnected-(U1-PE1-Pad98)") (class "Default")
      (node (ref "U1") (pin "98") (pinfunction "PE1_98") (pintype "passive"))
    )
    (net (code "100") (name "unconnected-(U4-ENA-Pad5)") (class "Default")
      (node (ref "U4") (pin "5") (pinfunction "ENA_5") (pintype "passive"))
    )
    (net (code "101") (name "unconnected-(U4-NC-Pad2)") (class "Default")
      (node (ref "U4") (pin "2") (pinfunction "NC_2") (pintype "passive"))
    )
    (net (code "102") (name "unconnected-(U4-NC-Pad3)") (class "Default")
      (node (ref "U4") (pin "3") (pinfunction "NC_3") (pintype "passive"))
    )
  )
)
